# esp-box-emu.net
KiCad netlist of a schematic drawn in EAGLE
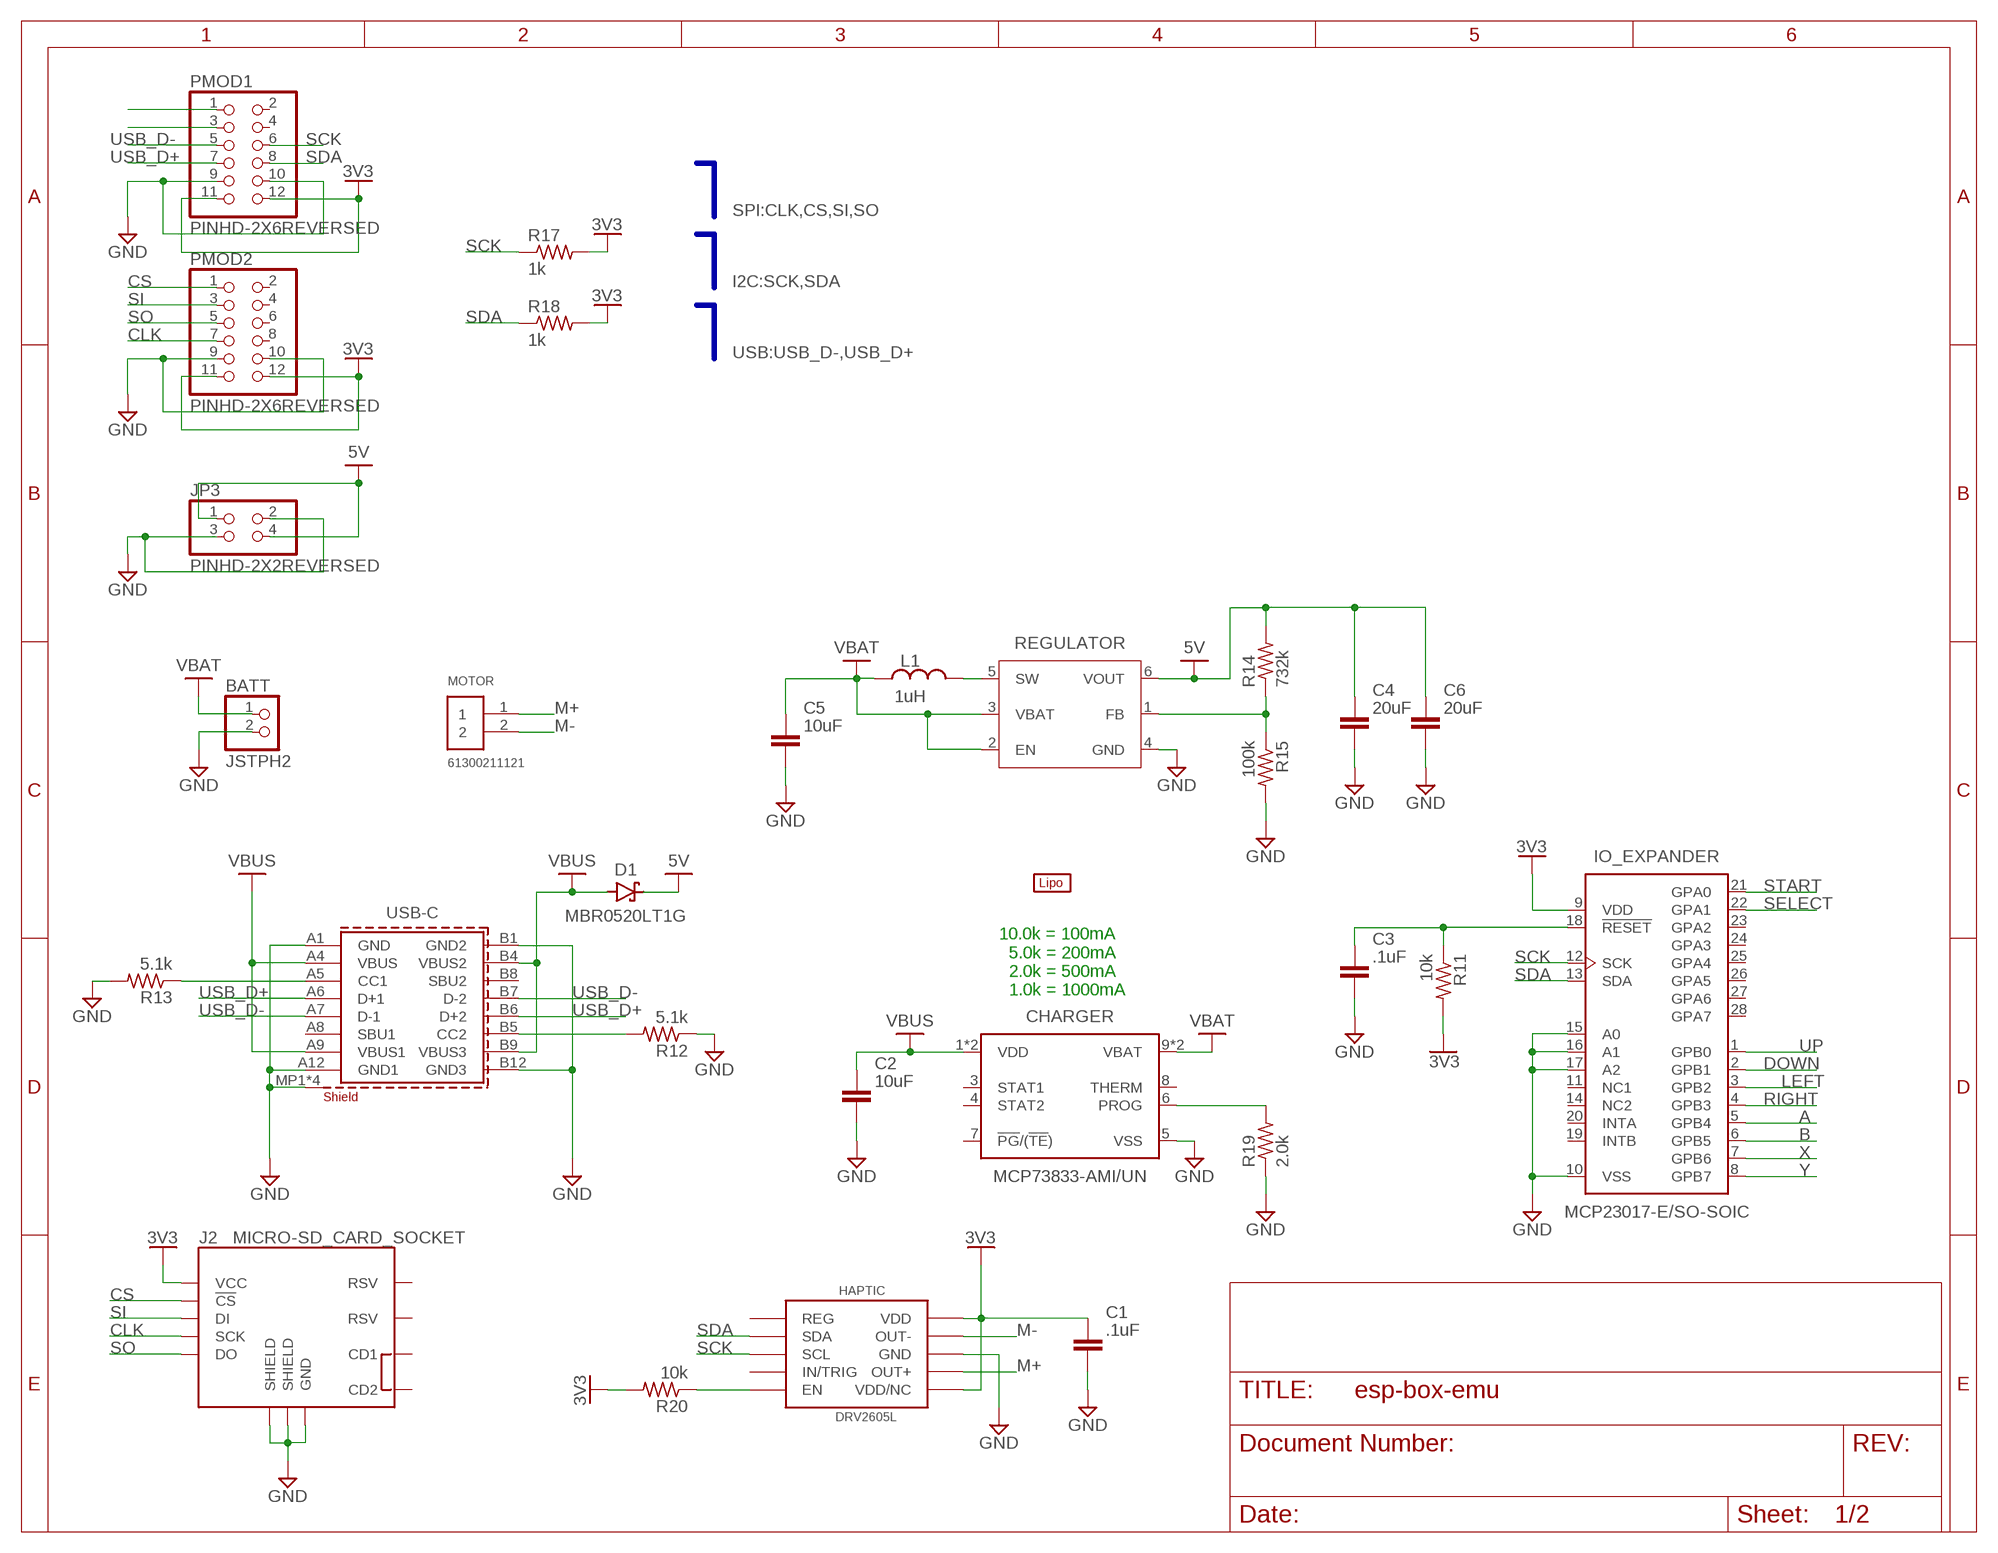
[diagram p0: schematic, sheet 1]
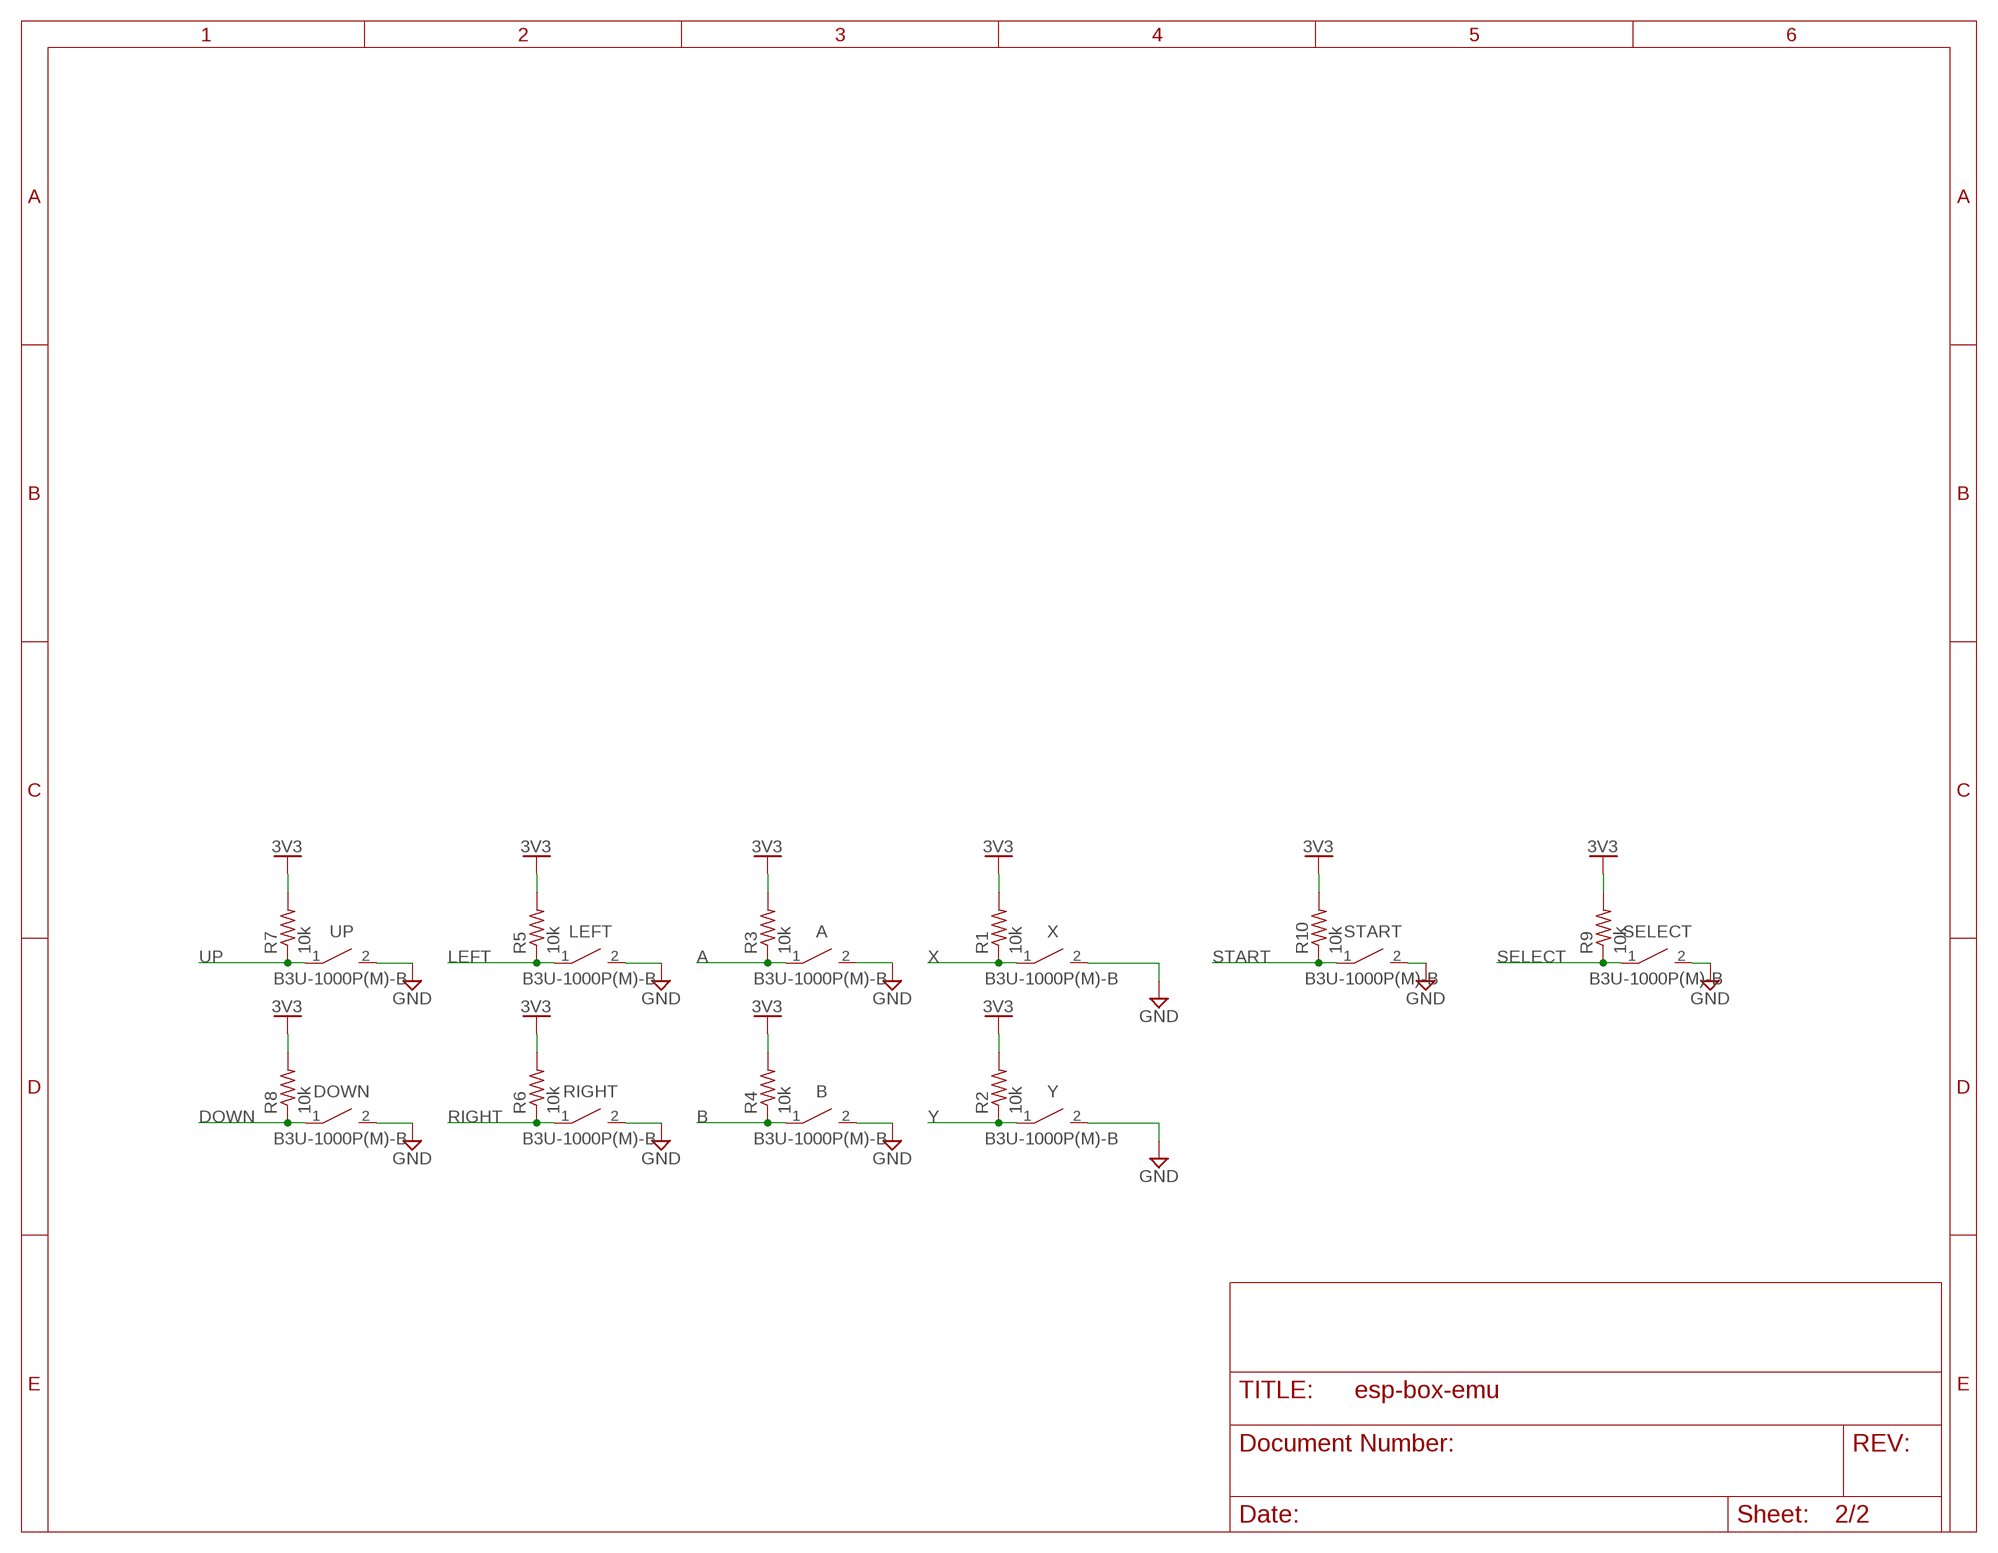
[diagram p1: schematic, sheet 2]

(export (version "E")
  (design (tool "Eeschema 10.0.6"))
  (components
    (comp (ref "A")
      (value "B3U-1000P(M)-B")
      (footprint "eagle-import:B3U-1000P(M)-B")
      (fields (field (name "MANUFACTURER") "OMRON"))
      (libsource (lib "eagle-import") (part "B3U-X0001000P(M)-BB3U-1000P(M)-B"))
    )
    (comp (ref "B")
      (value "B3U-1000P(M)-B")
      (footprint "eagle-import:B3U-1000P(M)-B")
      (fields (field (name "MANUFACTURER") "OMRON"))
      (libsource (lib "eagle-import") (part "B3U-X0001000P(M)-BB3U-1000P(M)-B"))
    )
    (comp (ref "DOWN")
      (value "B3U-1000P(M)-B")
      (footprint "eagle-import:B3U-1000P(M)-B")
      (fields (field (name "MANUFACTURER") "OMRON"))
      (libsource (lib "eagle-import") (part "B3U-X0001000P(M)-BB3U-1000P(M)-B"))
    )
    (comp (ref "LEFT")
      (value "B3U-1000P(M)-B")
      (footprint "eagle-import:B3U-1000P(M)-B")
      (fields (field (name "MANUFACTURER") "OMRON"))
      (libsource (lib "eagle-import") (part "B3U-X0001000P(M)-BB3U-1000P(M)-B"))
    )
    (comp (ref "R1")
      (value "10k")
      (footprint "eagle-import:RESC1608X60")
      (libsource (lib "eagle-import") (part "R-USCHIP-0603(1608-METRIC)_"))
    )
    (comp (ref "R2")
      (value "10k")
      (footprint "eagle-import:RESC1608X60")
      (libsource (lib "eagle-import") (part "R-USCHIP-0603(1608-METRIC)_"))
    )
    (comp (ref "R3")
      (value "10k")
      (footprint "eagle-import:RESC1608X60")
      (libsource (lib "eagle-import") (part "R-USCHIP-0603(1608-METRIC)_"))
    )
    (comp (ref "R4")
      (value "10k")
      (footprint "eagle-import:RESC1608X60")
      (libsource (lib "eagle-import") (part "R-USCHIP-0603(1608-METRIC)_"))
    )
    (comp (ref "R5")
      (value "10k")
      (footprint "eagle-import:RESC1608X60")
      (libsource (lib "eagle-import") (part "R-USCHIP-0603(1608-METRIC)_"))
    )
    (comp (ref "R6")
      (value "10k")
      (footprint "eagle-import:RESC1608X60")
      (libsource (lib "eagle-import") (part "R-USCHIP-0603(1608-METRIC)_"))
    )
    (comp (ref "R7")
      (value "10k")
      (footprint "eagle-import:RESC1608X60")
      (libsource (lib "eagle-import") (part "R-USCHIP-0603(1608-METRIC)_"))
    )
    (comp (ref "R8")
      (value "10k")
      (footprint "eagle-import:RESC1608X60")
      (libsource (lib "eagle-import") (part "R-USCHIP-0603(1608-METRIC)_"))
    )
    (comp (ref "R9")
      (value "10k")
      (footprint "eagle-import:RESC1608X60")
      (libsource (lib "eagle-import") (part "R-USCHIP-0603(1608-METRIC)_"))
    )
    (comp (ref "R10")
      (value "10k")
      (footprint "eagle-import:RESC1608X60")
      (libsource (lib "eagle-import") (part "R-USCHIP-0603(1608-METRIC)_"))
    )
    (comp (ref "RIGHT")
      (value "B3U-1000P(M)-B")
      (footprint "eagle-import:B3U-1000P(M)-B")
      (fields (field (name "MANUFACTURER") "OMRON"))
      (libsource (lib "eagle-import") (part "B3U-X0001000P(M)-BB3U-1000P(M)-B"))
    )
    (comp (ref "SELECT")
      (value "B3U-1000P(M)-B")
      (footprint "eagle-import:B3U-1000P(M)-B")
      (fields (field (name "MANUFACTURER") "OMRON"))
      (libsource (lib "eagle-import") (part "B3U-X0001000P(M)-BB3U-1000P(M)-B"))
    )
    (comp (ref "START")
      (value "B3U-1000P(M)-B")
      (footprint "eagle-import:B3U-1000P(M)-B")
      (fields (field (name "MANUFACTURER") "OMRON"))
      (libsource (lib "eagle-import") (part "B3U-X0001000P(M)-BB3U-1000P(M)-B"))
    )
    (comp (ref "UP")
      (value "B3U-1000P(M)-B")
      (footprint "eagle-import:B3U-1000P(M)-B")
      (fields (field (name "MANUFACTURER") "OMRON"))
      (libsource (lib "eagle-import") (part "B3U-X0001000P(M)-BB3U-1000P(M)-B"))
    )
    (comp (ref "X")
      (value "B3U-1000P(M)-B")
      (footprint "eagle-import:B3U-1000P(M)-B")
      (fields (field (name "MANUFACTURER") "OMRON"))
      (libsource (lib "eagle-import") (part "B3U-X0001000P(M)-BB3U-1000P(M)-B"))
    )
    (comp (ref "Y")
      (value "B3U-1000P(M)-B")
      (footprint "eagle-import:B3U-1000P(M)-B")
      (fields (field (name "MANUFACTURER") "OMRON"))
      (libsource (lib "eagle-import") (part "B3U-X0001000P(M)-BB3U-1000P(M)-B"))
    )
    (comp (ref "BATT")
      (value "JSTPH2")
      (footprint "eagle-import:JSTPH2")
      (libsource (lib "eagle-import") (part "JSTPH2"))
    )
    (comp (ref "BT1")
      (value "LIPO-OUTLINE1100")
      (footprint "eagle-import:LIPO-1000")
      (libsource (lib "eagle-import") (part "LIPO-OUTLINE1100"))
    )
    (comp (ref "C1")
      (value ".1uF")
      (footprint "eagle-import:CAPC1608X85")
      (libsource (lib "eagle-import") (part "CCHIP-0603(1608-METRIC)_"))
    )
    (comp (ref "C2")
      (value "10uF")
      (footprint "eagle-import:CAPC1608X85")
      (libsource (lib "eagle-import") (part "CCHIP-0603(1608-METRIC)_"))
    )
    (comp (ref "C3")
      (value ".1uF")
      (footprint "eagle-import:CAPC1608X85")
      (libsource (lib "eagle-import") (part "CCHIP-0603(1608-METRIC)_"))
    )
    (comp (ref "C4")
      (value "20uF")
      (footprint "eagle-import:CAPC2012X110")
      (libsource (lib "eagle-import") (part "CCHIP-0805(2012-METRIC)_"))
    )
    (comp (ref "C5")
      (value "10uF")
      (footprint "eagle-import:CAPC1608X85")
      (libsource (lib "eagle-import") (part "CCHIP-0603(1608-METRIC)_"))
    )
    (comp (ref "C6")
      (value "20uF")
      (footprint "eagle-import:CAPC2012X110")
      (libsource (lib "eagle-import") (part "CCHIP-0805(2012-METRIC)_"))
    )
    (comp (ref "CHARGER")
      (value "MCP73833-AMI/UN")
      (footprint "eagle-import:SOP50P490X110-10")
      (fields (field (name "MANUFACTURER") "Microchip Technology"))
      (libsource (lib "eagle-import") (part "MCP73833-AMI/UN"))
    )
    (comp (ref "D1")
      (value "MBR0520LT1G")
      (footprint "eagle-import:SODFL3718X115")
      (fields (field (name "MANUFACTURER") "ON Semiconductor"))
      (libsource (lib "eagle-import") (part "SCHOTTKY_DO-219MBR0520LT1G"))
    )
    (comp (ref "HAPTIC")
      (value "DRV2605L")
      (footprint "eagle-import:VSSOP-10")
      (libsource (lib "eagle-import") (part "DRV2605L"))
    )
    (comp (ref "IO_EXPANDER")
      (value "MCP23017-E/SO-SOIC")
      (footprint "eagle-import:SOIC127P1030X265-28")
      (fields (field (name "MANUFACTURER") "Microchip Technology") (field (name "MPN") "MCP23017-E/SO"))
      (libsource (lib "eagle-import") (part "MCP23017-SOIC-E/SO"))
    )
    (comp (ref "J2")
      (value "MICRO-SD_CARD_SOCKET")
      (footprint "eagle-import:MICRO-SD-SOCKET")
      (libsource (lib "eagle-import") (part "MICRO-SD_CARD_SOCKET"))
    )
    (comp (ref "JP3")
      (value "PINHD-2X2REVERSED")
      (footprint "eagle-import:2X02_EDGE_REVERSED")
      (libsource (lib "eagle-import") (part "PINHD-2X2REVERSED"))
    )
    (comp (ref "L1")
      (value "1uH")
      (footprint "eagle-import:INDM3225X240")
      (libsource (lib "eagle-import") (part "LMOLDED-1210(3225-METRIC)_"))
    )
    (comp (ref "MOTOR")
      (value "61300211121")
      (footprint "eagle-import:61300211121")
      (fields
        (field (name "DIGI_KEY_PART_NUMBER") "732-5315-ND")
        (field (name "MANUFACTURER") "Wurth Electronics Inc.")
        (field (name "CREATED_BY") "PCBLayout.com")
      )
      (libsource (lib "eagle-import") (part "61300211121"))
    )
    (comp (ref "PMOD1")
      (value "PINHD-2X6REVERSED")
      (footprint "eagle-import:2X06_EDGE_REVERSED")
      (libsource (lib "eagle-import") (part "PINHD-2X6REVERSED"))
    )
    (comp (ref "PMOD2")
      (value "PINHD-2X6REVERSED")
      (footprint "eagle-import:2X06_EDGE_REVERSED")
      (libsource (lib "eagle-import") (part "PINHD-2X6REVERSED"))
    )
    (comp (ref "R11")
      (value "10k")
      (footprint "eagle-import:RESC1608X60")
      (libsource (lib "eagle-import") (part "R-USCHIP-0603(1608-METRIC)_"))
    )
    (comp (ref "R12")
      (value "5.1k")
      (footprint "eagle-import:RESC1608X60")
      (libsource (lib "eagle-import") (part "R-USCHIP-0603(1608-METRIC)_"))
    )
    (comp (ref "R13")
      (value "5.1k")
      (footprint "eagle-import:RESC1608X60")
      (libsource (lib "eagle-import") (part "R-USCHIP-0603(1608-METRIC)_"))
    )
    (comp (ref "R14")
      (value "732k")
      (footprint "eagle-import:RESC1608X60")
      (libsource (lib "eagle-import") (part "R-USCHIP-0603(1608-METRIC)_"))
    )
    (comp (ref "R15")
      (value "100k")
      (footprint "eagle-import:RESC1608X60")
      (libsource (lib "eagle-import") (part "R-USCHIP-0603(1608-METRIC)_"))
    )
    (comp (ref "R17")
      (value "1k")
      (footprint "eagle-import:RESC1608X60")
      (libsource (lib "eagle-import") (part "R-USCHIP-0603(1608-METRIC)_"))
    )
    (comp (ref "R18")
      (value "1k")
      (footprint "eagle-import:RESC1608X60")
      (libsource (lib "eagle-import") (part "R-USCHIP-0603(1608-METRIC)_"))
    )
    (comp (ref "R19")
      (value "2.0k")
      (footprint "eagle-import:RESC1608X60")
      (libsource (lib "eagle-import") (part "R-USCHIP-0603(1608-METRIC)_"))
    )
    (comp (ref "R20")
      (value "10k")
      (footprint "eagle-import:RESC1608X60")
      (libsource (lib "eagle-import") (part "R-USCHIP-0603(1608-METRIC)_"))
    )
    (comp (ref "REGULATOR")
      (value "TPS61070")
      (footprint "eagle-import:SOT563")
      (libsource (lib "eagle-import") (part "TPS61023"))
    )
    (comp (ref "USB-C")
      (value "629722000214")
      (footprint "eagle-import:USB4110GFA")
      (libsource (lib "eagle-import") (part "629722000214SMD"))
    )
  )
  (nets
    (net (code "7") (name "3V3") (class "Default")
      (node (ref "C1") (pin "1") (pinfunction "1_1") (pintype "passive"))
      (node (ref "HAPTIC") (pin "P$10") (pinfunction "VDD_P$10") (pintype "bidirectional"))
      (node (ref "HAPTIC") (pin "P$6") (pinfunction "VDD/NC_P$6") (pintype "bidirectional"))
      (node (ref "IO_EXPANDER") (pin "9") (pinfunction "VDD_9") (pintype "power_in"))
      (node (ref "J2") (pin "VCC") (pinfunction "VCC_VCC") (pintype "bidirectional"))
      (node (ref "PMOD1") (pin "11") (pinfunction "11_11") (pintype "passive"))
      (node (ref "PMOD1") (pin "12") (pinfunction "12_12") (pintype "passive"))
      (node (ref "PMOD2") (pin "11") (pinfunction "11_11") (pintype "passive"))
      (node (ref "PMOD2") (pin "12") (pinfunction "12_12") (pintype "passive"))
      (node (ref "R1") (pin "2") (pinfunction "2_2") (pintype "passive"))
      (node (ref "R10") (pin "2") (pinfunction "2_2") (pintype "passive"))
      (node (ref "R11") (pin "2") (pinfunction "2_2") (pintype "passive"))
      (node (ref "R17") (pin "2") (pinfunction "2_2") (pintype "passive"))
      (node (ref "R18") (pin "2") (pinfunction "2_2") (pintype "passive"))
      (node (ref "R2") (pin "2") (pinfunction "2_2") (pintype "passive"))
      (node (ref "R20") (pin "2") (pinfunction "2_2") (pintype "passive"))
      (node (ref "R3") (pin "2") (pinfunction "2_2") (pintype "passive"))
      (node (ref "R4") (pin "2") (pinfunction "2_2") (pintype "passive"))
      (node (ref "R5") (pin "2") (pinfunction "2_2") (pintype "passive"))
      (node (ref "R6") (pin "2") (pinfunction "2_2") (pintype "passive"))
      (node (ref "R7") (pin "2") (pinfunction "2_2") (pintype "passive"))
      (node (ref "R8") (pin "2") (pinfunction "2_2") (pintype "passive"))
      (node (ref "R9") (pin "2") (pinfunction "2_2") (pintype "passive"))
    )
    (net (code "8") (name "5V") (class "Default")
      (node (ref "C4") (pin "1") (pinfunction "1_1") (pintype "passive"))
      (node (ref "C6") (pin "1") (pinfunction "1_1") (pintype "passive"))
      (node (ref "D1") (pin "1") (pinfunction "C_1") (pintype "passive"))
      (node (ref "JP3") (pin "1") (pinfunction "1_1") (pintype "passive"))
      (node (ref "JP3") (pin "4") (pinfunction "4_4") (pintype "passive"))
      (node (ref "R14") (pin "2") (pinfunction "2_2") (pintype "passive"))
      (node (ref "REGULATOR") (pin "6") (pinfunction "VOUT_6") (pintype "output"))
    )
    (net (code "9") (name "A") (class "Default")
      (node (ref "A") (pin "1") (pinfunction "1_1") (pintype "bidirectional"))
      (node (ref "IO_EXPANDER") (pin "5") (pinfunction "GPB4_5") (pintype "bidirectional"))
      (node (ref "R3") (pin "1") (pinfunction "1_1") (pintype "passive"))
    )
    (net (code "10") (name "B") (class "Default")
      (node (ref "B") (pin "1") (pinfunction "1_1") (pintype "bidirectional"))
      (node (ref "IO_EXPANDER") (pin "6") (pinfunction "GPB5_6") (pintype "bidirectional"))
      (node (ref "R4") (pin "1") (pinfunction "1_1") (pintype "passive"))
    )
    (net (code "11") (name "CLK") (class "Default")
      (node (ref "J2") (pin "SCLK") (pinfunction "SCK_SCLK") (pintype "bidirectional"))
      (node (ref "PMOD2") (pin "7") (pinfunction "7_7") (pintype "passive"))
    )
    (net (code "12") (name "CS") (class "Default")
      (node (ref "J2") (pin "CS") (pinfunction "~{CS}_CS") (pintype "bidirectional"))
      (node (ref "PMOD2") (pin "1") (pinfunction "1_1") (pintype "passive"))
    )
    (net (code "13") (name "DOWN") (class "Default")
      (node (ref "DOWN") (pin "1") (pinfunction "1_1") (pintype "bidirectional"))
      (node (ref "IO_EXPANDER") (pin "2") (pinfunction "GPB1_2") (pintype "bidirectional"))
      (node (ref "R8") (pin "1") (pinfunction "1_1") (pintype "passive"))
    )
    (net (code "14") (name "GND") (class "Default")
      (node (ref "A") (pin "2") (pinfunction "2_2") (pintype "bidirectional"))
      (node (ref "B") (pin "2") (pinfunction "2_2") (pintype "bidirectional"))
      (node (ref "BATT") (pin "2") (pinfunction "2_2") (pintype "passive"))
      (node (ref "C1") (pin "2") (pinfunction "2_2") (pintype "passive"))
      (node (ref "C2") (pin "2") (pinfunction "2_2") (pintype "passive"))
      (node (ref "C3") (pin "2") (pinfunction "2_2") (pintype "passive"))
      (node (ref "C4") (pin "2") (pinfunction "2_2") (pintype "passive"))
      (node (ref "C5") (pin "2") (pinfunction "2_2") (pintype "passive"))
      (node (ref "C6") (pin "2") (pinfunction "2_2") (pintype "passive"))
      (node (ref "CHARGER") (pin "5") (pinfunction "VSS_5") (pintype "power_in"))
      (node (ref "DOWN") (pin "2") (pinfunction "2_2") (pintype "bidirectional"))
      (node (ref "HAPTIC") (pin "P$8") (pinfunction "GND_P$8") (pintype "bidirectional"))
      (node (ref "IO_EXPANDER") (pin "10") (pinfunction "VSS_10") (pintype "power_in"))
      (node (ref "IO_EXPANDER") (pin "15") (pinfunction "A0_15") (pintype "input"))
      (node (ref "IO_EXPANDER") (pin "16") (pinfunction "A1_16") (pintype "input"))
      (node (ref "IO_EXPANDER") (pin "17") (pinfunction "A2_17") (pintype "input"))
      (node (ref "J2") (pin "GND") (pinfunction "GND_GND") (pintype "bidirectional"))
      (node (ref "J2") (pin "GND1") (pinfunction "SHIELD_GND1") (pintype "bidirectional"))
      (node (ref "J2") (pin "GND3") (pinfunction "SHIELD_GND3") (pintype "bidirectional"))
      (node (ref "JP3") (pin "2") (pinfunction "2_2") (pintype "passive"))
      (node (ref "JP3") (pin "3") (pinfunction "3_3") (pintype "passive"))
      (node (ref "LEFT") (pin "2") (pinfunction "2_2") (pintype "bidirectional"))
      (node (ref "PMOD1") (pin "10") (pinfunction "10_10") (pintype "passive"))
      (node (ref "PMOD1") (pin "9") (pinfunction "9_9") (pintype "passive"))
      (node (ref "PMOD2") (pin "10") (pinfunction "10_10") (pintype "passive"))
      (node (ref "PMOD2") (pin "9") (pinfunction "9_9") (pintype "passive"))
      (node (ref "R12") (pin "1") (pinfunction "1_1") (pintype "passive"))
      (node (ref "R13") (pin "2") (pinfunction "2_2") (pintype "passive"))
      (node (ref "R15") (pin "2") (pinfunction "2_2") (pintype "passive"))
      (node (ref "R19") (pin "1") (pinfunction "1_1") (pintype "passive"))
      (node (ref "REGULATOR") (pin "4") (pinfunction "GND_4") (pintype "power_in"))
      (node (ref "RIGHT") (pin "2") (pinfunction "2_2") (pintype "bidirectional"))
      (node (ref "SELECT") (pin "2") (pinfunction "2_2") (pintype "bidirectional"))
      (node (ref "START") (pin "2") (pinfunction "2_2") (pintype "bidirectional"))
      (node (ref "UP") (pin "2") (pinfunction "2_2") (pintype "bidirectional"))
      (node (ref "USB-C") (pin "A1") (pinfunction "GND_A1") (pintype "passive"))
      (node (ref "USB-C") (pin "A12") (pinfunction "GND1_A12") (pintype "passive"))
      (node (ref "USB-C") (pin "B1") (pinfunction "GND2_B1") (pintype "passive"))
      (node (ref "USB-C") (pin "B12") (pinfunction "GND3_B12") (pintype "passive"))
      (node (ref "USB-C") (pin "MP1") (pinfunction "SHIELD_MP1") (pintype "passive"))
      (node (ref "USB-C") (pin "MP2") (pinfunction "SHIELD_MP2") (pintype "passive"))
      (node (ref "USB-C") (pin "MP3") (pinfunction "SHIELD_MP3") (pintype "passive"))
      (node (ref "USB-C") (pin "MP4") (pinfunction "SHIELD_MP4") (pintype "passive"))
      (node (ref "X") (pin "2") (pinfunction "2_2") (pintype "bidirectional"))
      (node (ref "Y") (pin "2") (pinfunction "2_2") (pintype "bidirectional"))
    )
    (net (code "15") (name "LEFT") (class "Default")
      (node (ref "IO_EXPANDER") (pin "3") (pinfunction "GPB2_3") (pintype "bidirectional"))
      (node (ref "LEFT") (pin "1") (pinfunction "1_1") (pintype "bidirectional"))
      (node (ref "R5") (pin "1") (pinfunction "1_1") (pintype "passive"))
    )
    (net (code "16") (name "M+") (class "Default")
      (node (ref "HAPTIC") (pin "P$7") (pinfunction "OUT+_P$7") (pintype "bidirectional"))
      (node (ref "MOTOR") (pin "1") (pinfunction "1_1") (pintype "passive"))
    )
    (net (code "17") (name "M-") (class "Default")
      (node (ref "HAPTIC") (pin "P$9") (pinfunction "OUT-_P$9") (pintype "bidirectional"))
      (node (ref "MOTOR") (pin "2") (pinfunction "2_2") (pintype "passive"))
    )
    (net (code "18") (name "Net-(CHARGER-PROG)") (class "Default")
      (node (ref "CHARGER") (pin "6") (pinfunction "PROG_6") (pintype "input"))
      (node (ref "R19") (pin "2") (pinfunction "2_2") (pintype "passive"))
    )
    (net (code "19") (name "Net-(HAPTIC-EN)") (class "Default")
      (node (ref "HAPTIC") (pin "P$5") (pinfunction "EN_P$5") (pintype "bidirectional"))
      (node (ref "R20") (pin "1") (pinfunction "1_1") (pintype "passive"))
    )
    (net (code "20") (name "Net-(IO_EXPANDER-~{RESET})") (class "Default")
      (node (ref "C3") (pin "1") (pinfunction "1_1") (pintype "passive"))
      (node (ref "IO_EXPANDER") (pin "18") (pinfunction "~{RESET}_18") (pintype "input"))
      (node (ref "R11") (pin "1") (pinfunction "1_1") (pintype "passive"))
    )
    (net (code "21") (name "Net-(REGULATOR-FB)") (class "Default")
      (node (ref "R14") (pin "1") (pinfunction "1_1") (pintype "passive"))
      (node (ref "R15") (pin "1") (pinfunction "1_1") (pintype "passive"))
      (node (ref "REGULATOR") (pin "1") (pinfunction "FB_1") (pintype "input"))
    )
    (net (code "22") (name "Net-(REGULATOR-SW)") (class "Default")
      (node (ref "L1") (pin "2") (pinfunction "2_2") (pintype "passive"))
      (node (ref "REGULATOR") (pin "5") (pinfunction "SW_5") (pintype "input"))
    )
    (net (code "23") (name "Net-(USB-C-CC1)") (class "Default")
      (node (ref "R13") (pin "1") (pinfunction "1_1") (pintype "passive"))
      (node (ref "USB-C") (pin "A5") (pinfunction "CC1_A5") (pintype "passive"))
    )
    (net (code "24") (name "Net-(USB-C-CC2)") (class "Default")
      (node (ref "R12") (pin "2") (pinfunction "2_2") (pintype "passive"))
      (node (ref "USB-C") (pin "B5") (pinfunction "CC2_B5") (pintype "passive"))
    )
    (net (code "25") (name "RIGHT") (class "Default")
      (node (ref "IO_EXPANDER") (pin "4") (pinfunction "GPB3_4") (pintype "bidirectional"))
      (node (ref "R6") (pin "1") (pinfunction "1_1") (pintype "passive"))
      (node (ref "RIGHT") (pin "1") (pinfunction "1_1") (pintype "bidirectional"))
    )
    (net (code "26") (name "SCK") (class "Default")
      (node (ref "HAPTIC") (pin "P$2") (pinfunction "SCL_P$2") (pintype "bidirectional"))
      (node (ref "IO_EXPANDER") (pin "12") (pinfunction "SCK_12") (pintype "input"))
      (node (ref "PMOD1") (pin "6") (pinfunction "6_6") (pintype "passive"))
      (node (ref "R17") (pin "1") (pinfunction "1_1") (pintype "passive"))
    )
    (net (code "27") (name "SDA") (class "Default")
      (node (ref "HAPTIC") (pin "P$3") (pinfunction "SDA_P$3") (pintype "bidirectional"))
      (node (ref "IO_EXPANDER") (pin "13") (pinfunction "SDA_13") (pintype "bidirectional"))
      (node (ref "PMOD1") (pin "8") (pinfunction "8_8") (pintype "passive"))
      (node (ref "R18") (pin "1") (pinfunction "1_1") (pintype "passive"))
    )
    (net (code "28") (name "SELECT") (class "Default")
      (node (ref "IO_EXPANDER") (pin "22") (pinfunction "GPA1_22") (pintype "bidirectional"))
      (node (ref "R9") (pin "1") (pinfunction "1_1") (pintype "passive"))
      (node (ref "SELECT") (pin "1") (pinfunction "1_1") (pintype "bidirectional"))
    )
    (net (code "29") (name "SI") (class "Default")
      (node (ref "J2") (pin "DI") (pinfunction "DI_DI") (pintype "bidirectional"))
      (node (ref "PMOD2") (pin "3") (pinfunction "3_3") (pintype "passive"))
    )
    (net (code "30") (name "SO") (class "Default")
      (node (ref "J2") (pin "DO") (pinfunction "DO_DO") (pintype "bidirectional"))
      (node (ref "PMOD2") (pin "5") (pinfunction "5_5") (pintype "passive"))
    )
    (net (code "31") (name "START") (class "Default")
      (node (ref "IO_EXPANDER") (pin "21") (pinfunction "GPA0_21") (pintype "bidirectional"))
      (node (ref "R10") (pin "1") (pinfunction "1_1") (pintype "passive"))
      (node (ref "START") (pin "1") (pinfunction "1_1") (pintype "bidirectional"))
    )
    (net (code "32") (name "UP") (class "Default")
      (node (ref "IO_EXPANDER") (pin "1") (pinfunction "GPB0_1") (pintype "bidirectional"))
      (node (ref "R7") (pin "1") (pinfunction "1_1") (pintype "passive"))
      (node (ref "UP") (pin "1") (pinfunction "1_1") (pintype "bidirectional"))
    )
    (net (code "33") (name "USB_D+") (class "Default")
      (node (ref "PMOD1") (pin "7") (pinfunction "7_7") (pintype "passive"))
      (node (ref "USB-C") (pin "A6") (pinfunction "D+1_A6") (pintype "passive"))
      (node (ref "USB-C") (pin "B6") (pinfunction "D+2_B6") (pintype "passive"))
    )
    (net (code "34") (name "USB_D-") (class "Default")
      (node (ref "PMOD1") (pin "5") (pinfunction "5_5") (pintype "passive"))
      (node (ref "USB-C") (pin "A7") (pinfunction "D-1_A7") (pintype "passive"))
      (node (ref "USB-C") (pin "B7") (pinfunction "D-2_B7") (pintype "passive"))
    )
    (net (code "35") (name "VBAT") (class "Default")
      (node (ref "BATT") (pin "1") (pinfunction "1_1") (pintype "passive"))
      (node (ref "C5") (pin "1") (pinfunction "1_1") (pintype "passive"))
      (node (ref "CHARGER") (pin "10") (pinfunction "VBAT_10") (pintype "output"))
      (node (ref "CHARGER") (pin "9") (pinfunction "VBAT_9") (pintype "output"))
      (node (ref "L1") (pin "1") (pinfunction "1_1") (pintype "passive"))
      (node (ref "REGULATOR") (pin "2") (pinfunction "EN_2") (pintype "input"))
      (node (ref "REGULATOR") (pin "3") (pinfunction "VBAT_3") (pintype "input"))
    )
    (net (code "36") (name "VBUS") (class "Default")
      (node (ref "C2") (pin "1") (pinfunction "1_1") (pintype "passive"))
      (node (ref "CHARGER") (pin "1") (pinfunction "VDD_1") (pintype "power_in"))
      (node (ref "CHARGER") (pin "2") (pinfunction "VDD_2") (pintype "power_in"))
      (node (ref "D1") (pin "2") (pinfunction "A_2") (pintype "passive"))
      (node (ref "USB-C") (pin "A4") (pinfunction "VBUS_A4") (pintype "passive"))
      (node (ref "USB-C") (pin "A9") (pinfunction "VBUS1_A9") (pintype "passive"))
      (node (ref "USB-C") (pin "B4") (pinfunction "VBUS2_B4") (pintype "passive"))
      (node (ref "USB-C") (pin "B9") (pinfunction "VBUS3_B9") (pintype "passive"))
    )
    (net (code "37") (name "X") (class "Default")
      (node (ref "IO_EXPANDER") (pin "7") (pinfunction "GPB6_7") (pintype "bidirectional"))
      (node (ref "R1") (pin "1") (pinfunction "1_1") (pintype "passive"))
      (node (ref "X") (pin "1") (pinfunction "1_1") (pintype "bidirectional"))
    )
    (net (code "38") (name "Y") (class "Default")
      (node (ref "IO_EXPANDER") (pin "8") (pinfunction "GPB7_8") (pintype "bidirectional"))
      (node (ref "R2") (pin "1") (pinfunction "1_1") (pintype "passive"))
      (node (ref "Y") (pin "1") (pinfunction "1_1") (pintype "bidirectional"))
    )
    (net (code "39") (name "unconnected-(CHARGER-STAT1-Pad3)") (class "Default")
      (node (ref "CHARGER") (pin "3") (pinfunction "STAT1_3") (pintype "output"))
    )
    (net (code "40") (name "unconnected-(CHARGER-STAT2-Pad4)") (class "Default")
      (node (ref "CHARGER") (pin "4") (pinfunction "STAT2_4") (pintype "output"))
    )
    (net (code "41") (name "unconnected-(CHARGER-THERM-Pad8)") (class "Default")
      (node (ref "CHARGER") (pin "8") (pinfunction "THERM_8") (pintype "input"))
    )
    (net (code "42") (name "unconnected-(CHARGER-~{PG}{slash}(~{TE})-Pad7)") (class "Default")
      (node (ref "CHARGER") (pin "7") (pinfunction "~{PG}/(~{TE})_7") (pintype "bidirectional"))
    )
    (net (code "43") (name "unconnected-(HAPTIC-IN{slash}TRIG-PadP$4)") (class "Default")
      (node (ref "HAPTIC") (pin "P$4") (pinfunction "IN/TRIG_P$4") (pintype "bidirectional"))
    )
    (net (code "44") (name "unconnected-(HAPTIC-REG-PadP$1)") (class "Default")
      (node (ref "HAPTIC") (pin "P$1") (pinfunction "REG_P$1") (pintype "bidirectional"))
    )
    (net (code "45") (name "unconnected-(IO_EXPANDER-GPA2-Pad23)") (class "Default")
      (node (ref "IO_EXPANDER") (pin "23") (pinfunction "GPA2_23") (pintype "bidirectional"))
    )
    (net (code "46") (name "unconnected-(IO_EXPANDER-GPA3-Pad24)") (class "Default")
      (node (ref "IO_EXPANDER") (pin "24") (pinfunction "GPA3_24") (pintype "bidirectional"))
    )
    (net (code "47") (name "unconnected-(IO_EXPANDER-GPA4-Pad25)") (class "Default")
      (node (ref "IO_EXPANDER") (pin "25") (pinfunction "GPA4_25") (pintype "bidirectional"))
    )
    (net (code "48") (name "unconnected-(IO_EXPANDER-GPA5-Pad26)") (class "Default")
      (node (ref "IO_EXPANDER") (pin "26") (pinfunction "GPA5_26") (pintype "bidirectional"))
    )
    (net (code "49") (name "unconnected-(IO_EXPANDER-GPA6-Pad27)") (class "Default")
      (node (ref "IO_EXPANDER") (pin "27") (pinfunction "GPA6_27") (pintype "bidirectional"))
    )
    (net (code "50") (name "unconnected-(IO_EXPANDER-GPA7-Pad28)") (class "Default")
      (node (ref "IO_EXPANDER") (pin "28") (pinfunction "GPA7_28") (pintype "bidirectional"))
    )
    (net (code "51") (name "unconnected-(IO_EXPANDER-INTA-Pad20)") (class "Default")
      (node (ref "IO_EXPANDER") (pin "20") (pinfunction "INTA_20") (pintype "output"))
    )
    (net (code "52") (name "unconnected-(IO_EXPANDER-INTB-Pad19)") (class "Default")
      (node (ref "IO_EXPANDER") (pin "19") (pinfunction "INTB_19") (pintype "output"))
    )
    (net (code "53") (name "unconnected-(IO_EXPANDER-NC1-Pad11)") (class "Default")
      (node (ref "IO_EXPANDER") (pin "11") (pinfunction "NC1_11") (pintype "no_connect"))
    )
    (net (code "54") (name "unconnected-(IO_EXPANDER-NC2-Pad14)") (class "Default")
      (node (ref "IO_EXPANDER") (pin "14") (pinfunction "NC2_14") (pintype "no_connect"))
    )
    (net (code "55") (name "unconnected-(J2-PadCD1)") (class "Default")
      (node (ref "J2") (pin "CD1") (pinfunction "CD1_CD1") (pintype "bidirectional"))
    )
    (net (code "56") (name "unconnected-(J2-PadCD2)") (class "Default")
      (node (ref "J2") (pin "CD2") (pinfunction "CD2_CD2") (pintype "bidirectional"))
    )
    (net (code "57") (name "unconnected-(J2-RSV-PadRSV1)") (class "Default")
      (node (ref "J2") (pin "RSV1") (pinfunction "RSV_RSV1") (pintype "bidirectional"))
    )
    (net (code "58") (name "unconnected-(J2-RSV-PadRSV2)") (class "Default")
      (node (ref "J2") (pin "RSV2") (pinfunction "RSV_RSV2") (pintype "bidirectional"))
    )
    (net (code "59") (name "unconnected-(PMOD1-Pad1)") (class "Default")
      (node (ref "PMOD1") (pin "1") (pinfunction "1_1") (pintype "passive"))
    )
    (net (code "60") (name "unconnected-(PMOD1-Pad2)") (class "Default")
      (node (ref "PMOD1") (pin "2") (pinfunction "2_2") (pintype "passive"))
    )
    (net (code "61") (name "unconnected-(PMOD1-Pad3)") (class "Default")
      (node (ref "PMOD1") (pin "3") (pinfunction "3_3") (pintype "passive"))
    )
    (net (code "62") (name "unconnected-(PMOD1-Pad4)") (class "Default")
      (node (ref "PMOD1") (pin "4") (pinfunction "4_4") (pintype "passive"))
    )
    (net (code "63") (name "unconnected-(PMOD2-Pad2)") (class "Default")
      (node (ref "PMOD2") (pin "2") (pinfunction "2_2") (pintype "passive"))
    )
    (net (code "64") (name "unconnected-(PMOD2-Pad4)") (class "Default")
      (node (ref "PMOD2") (pin "4") (pinfunction "4_4") (pintype "passive"))
    )
    (net (code "65") (name "unconnected-(PMOD2-Pad6)") (class "Default")
      (node (ref "PMOD2") (pin "6") (pinfunction "6_6") (pintype "passive"))
    )
    (net (code "66") (name "unconnected-(PMOD2-Pad8)") (class "Default")
      (node (ref "PMOD2") (pin "8") (pinfunction "8_8") (pintype "passive"))
    )
    (net (code "67") (name "unconnected-(USB-C-SBU1-PadA8)") (class "Default")
      (node (ref "USB-C") (pin "A8") (pinfunction "SBU1_A8") (pintype "passive"))
    )
    (net (code "68") (name "unconnected-(USB-C-SBU2-PadB8)") (class "Default")
      (node (ref "USB-C") (pin "B8") (pinfunction "SBU2_B8") (pintype "passive"))
    )
  )
)
